# femtoUSB_r1_0_1.net
KiCad netlist of a schematic drawn in EAGLE
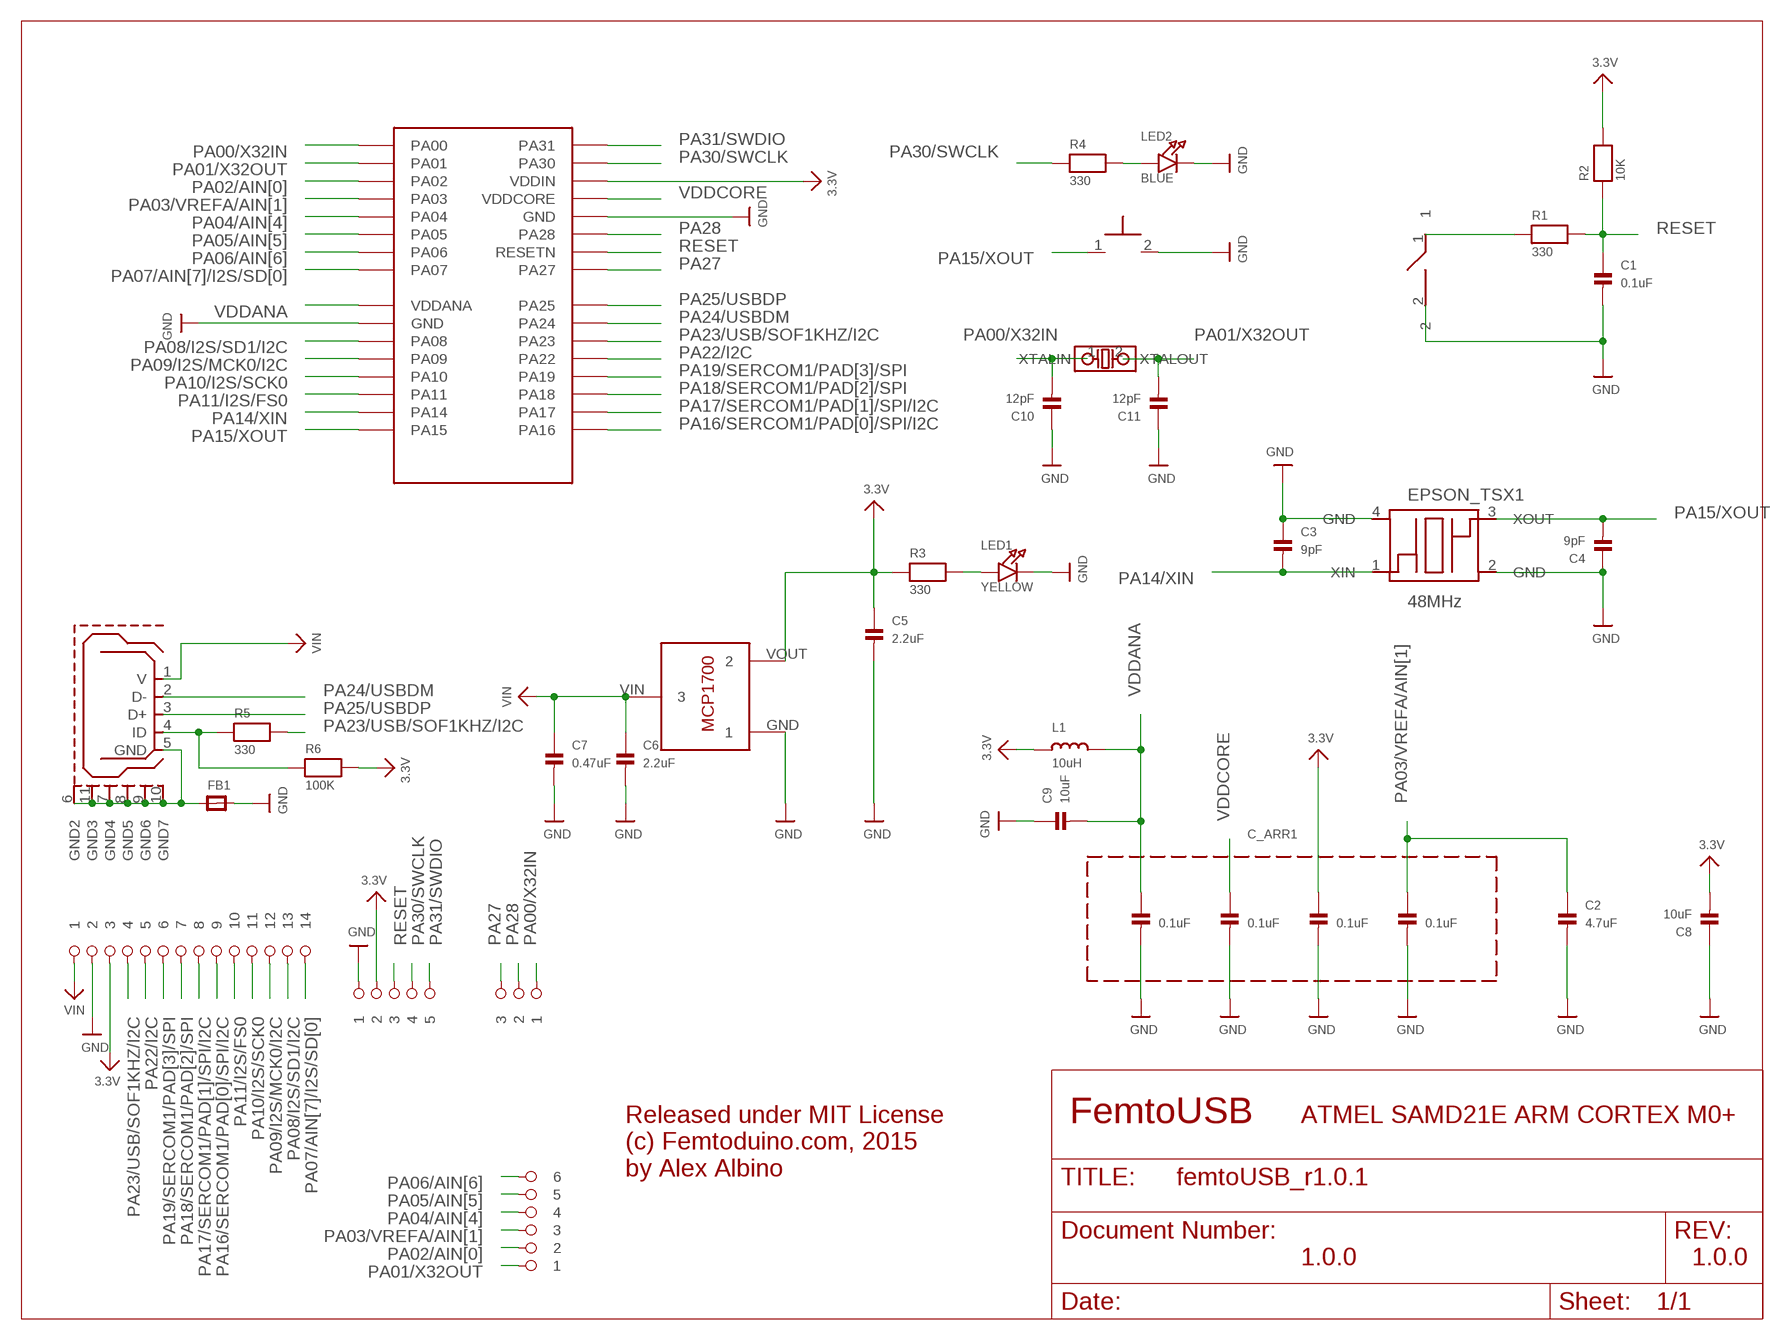
[diagram p0: schematic, sheet 1]

(export (version "E")
  (design (tool "Eeschema 10.0.6"))
  (components
    (comp (ref "BTN")
      (value "OMRON B3U-300P(M)")
      (footprint "eagle-import:SPST_SMD")
      (libsource (lib "eagle-import") (part "SPST_SMD"))
    )
    (comp (ref "C1")
      (value "0.1uF")
      (footprint "eagle-import:_0402MP")
      (libsource (lib "eagle-import") (part "CAP_CERAMIC_0402MP"))
    )
    (comp (ref "C2")
      (value "4.7uF")
      (footprint "eagle-import:_0402MP")
      (libsource (lib "eagle-import") (part "CAP_CERAMIC_0402MP"))
    )
    (comp (ref "C3")
      (value "9pF")
      (footprint "eagle-import:_0402MP")
      (libsource (lib "eagle-import") (part "CAP_CERAMIC_0402MP"))
    )
    (comp (ref "C4")
      (value "9pF")
      (footprint "eagle-import:_0402MP")
      (libsource (lib "eagle-import") (part "CAP_CERAMIC_0402MP"))
    )
    (comp (ref "C5")
      (value "2.2uF")
      (footprint "eagle-import:_0402MP")
      (libsource (lib "eagle-import") (part "CAP_CERAMIC_0402MP"))
    )
    (comp (ref "C6")
      (value "2.2uF")
      (footprint "eagle-import:_0402MP")
      (libsource (lib "eagle-import") (part "CAP_CERAMIC_0402MP"))
    )
    (comp (ref "C7")
      (value "0.47uF")
      (footprint "eagle-import:_0402MP")
      (libsource (lib "eagle-import") (part "CAP_CERAMIC_0402MP"))
    )
    (comp (ref "C8")
      (value "10uF")
      (footprint "eagle-import:_0402MP")
      (libsource (lib "eagle-import") (part "CAP_CERAMIC_0402MP"))
    )
    (comp (ref "C9")
      (value "10uF")
      (footprint "eagle-import:_0402MP")
      (libsource (lib "eagle-import") (part "CAP_CERAMIC_0402MP"))
    )
    (comp (ref "C10")
      (value "12pF")
      (footprint "eagle-import:_0402MP")
      (libsource (lib "eagle-import") (part "CAP_CERAMIC_0402MP"))
    )
    (comp (ref "C11")
      (value "12pF")
      (footprint "eagle-import:_0402MP")
      (libsource (lib "eagle-import") (part "CAP_CERAMIC_0402MP"))
    )
    (comp (ref "C_ARR1")
      (value "0.1uF")
      (footprint "eagle-import:CAPACITOR_ARRAY_1206_MONO_1X4")
      (libsource (lib "eagle-import") (part "KEMET_CERAMIC_CAPACITOR_ARRAY_1X4"))
    )
    (comp (ref "EPSON_TSX1")
      (value "48MHz")
      (footprint "eagle-import:TSX-3225")
      (fields (field (name "DIGIKEY_PART") "TSX-3225 32.0000MF15X-B-ND"))
      (libsource (lib "eagle-import") (part "TSX-3225"))
    )
    (comp (ref "FB1")
      (value "FERRITE_0603MP")
      (footprint "eagle-import:_0603MP")
      (libsource (lib "eagle-import") (part "FERRITE_0603MP"))
    )
    (comp (ref "IC1")
      (value "ATSAMD21E18A-MUT")
      (footprint "eagle-import:QFN32")
      (libsource (lib "eagle-import") (part "ATSAMD21E18A-MUT"))
    )
    (comp (ref "L1")
      (value "10uH")
      (footprint "eagle-import:_0603MP")
      (libsource (lib "eagle-import") (part "INDUCTOR_0603MP"))
    )
    (comp (ref "LDO_VREG")
      (value "MCP1700T-3302E/TT")
      (footprint "eagle-import:MCP1700T-3302E_TT")
      (libsource (lib "eagle-import") (part "MCP1700T-3302E/TT"))
    )
    (comp (ref "LED1")
      (value "YELLOW")
      (footprint "eagle-import:CHIPLED_0603_NOOUTLINE")
      (libsource (lib "eagle-import") (part "LED0603_NOOUTLINE"))
    )
    (comp (ref "LED2")
      (value "BLUE")
      (footprint "eagle-import:CHIPLED_0603_NOOUTLINE")
      (libsource (lib "eagle-import") (part "LED0603_NOOUTLINE"))
    )
    (comp (ref "MICRO_B_USB")
      (value "USB_MICROB")
      (footprint "eagle-import:USB_MICROB_PACKAGE")
      (libsource (lib "eagle-import") (part "USB_MICROB"))
    )
    (comp (ref "R1")
      (value "330")
      (footprint "eagle-import:_0402MP")
      (libsource (lib "eagle-import") (part "RESISTOR_0402MP"))
    )
    (comp (ref "R2")
      (value "10K")
      (footprint "eagle-import:_0402MP")
      (libsource (lib "eagle-import") (part "RESISTOR_0402MP"))
    )
    (comp (ref "R3")
      (value "330")
      (footprint "eagle-import:_0402MP")
      (libsource (lib "eagle-import") (part "RESISTOR_0402MP"))
    )
    (comp (ref "R4")
      (value "330")
      (footprint "eagle-import:_0402MP")
      (libsource (lib "eagle-import") (part "RESISTOR_0402MP"))
    )
    (comp (ref "R5")
      (value "330")
      (footprint "eagle-import:_0402MP")
      (libsource (lib "eagle-import") (part "RESISTOR_0402MP"))
    )
    (comp (ref "R6")
      (value "100K")
      (footprint "eagle-import:_0402MP")
      (libsource (lib "eagle-import") (part "RESISTOR_0402MP"))
    )
    (comp (ref "U$6")
      (value "1X14_ROUND")
      (footprint "eagle-import:1X14_ROUND")
      (libsource (lib "eagle-import") (part "1X14_ROUND"))
    )
    (comp (ref "U$7")
      (value "1X3_ROUND")
      (footprint "eagle-import:1X3_ROUND")
      (libsource (lib "eagle-import") (part "1X3_ROUND"))
    )
    (comp (ref "U$9")
      (value "1X5_ROUND")
      (footprint "eagle-import:1X5_ROUND")
      (libsource (lib "eagle-import") (part "1X5_ROUND"))
    )
    (comp (ref "U$12")
      (value "1X6_ROUND")
      (footprint "eagle-import:1X6_ROUND")
      (libsource (lib "eagle-import") (part "1X6_ROUND"))
    )
    (comp (ref "U$40")
      (value "ABS06-107-32.768KHZ-T")
      (footprint "eagle-import:ABS06-107-32.768KHZ-T")
      (libsource (lib "eagle-import") (part "ABS06-107-32.768KHZ-T"))
    )
    (comp (ref "U$43")
      (value "TACTILE_SWITCH_NO_GND_NO_BOSS")
      (footprint "eagle-import:SIDE_ACT_NO_GND_NO_BOSS")
      (libsource (lib "eagle-import") (part "TACTILE_SWITCH_NO_GND_NO_BOSS"))
    )
  )
  (nets
    (net (code "1") (name "/PA00{slash}X32IN") (class "Default")
      (node (ref "C10") (pin "2") (pinfunction "P$2_2") (pintype "passive"))
      (node (ref "IC1") (pin "1") (pinfunction "PA00_1") (pintype "bidirectional"))
      (node (ref "U$40") (pin "1") (pinfunction "XTALIN_1") (pintype "bidirectional"))
      (node (ref "U$7") (pin "P$1") (pinfunction "1_P$1") (pintype "bidirectional"))
    )
    (net (code "2") (name "/PA01{slash}X32OUT") (class "Default")
      (node (ref "C11") (pin "2") (pinfunction "P$2_2") (pintype "passive"))
      (node (ref "IC1") (pin "2") (pinfunction "PA01_2") (pintype "bidirectional"))
      (node (ref "U$12") (pin "P$1") (pinfunction "1_P$1") (pintype "bidirectional"))
      (node (ref "U$40") (pin "2") (pinfunction "XTALOUT_2") (pintype "bidirectional"))
    )
    (net (code "3") (name "/PA02{slash}AIN[0]") (class "Default")
      (node (ref "IC1") (pin "3") (pinfunction "PA02_3") (pintype "bidirectional"))
      (node (ref "U$12") (pin "P$2") (pinfunction "2_P$2") (pintype "bidirectional"))
    )
    (net (code "4") (name "/PA03{slash}VREFA{slash}AIN[1]") (class "Default")
      (node (ref "C2") (pin "1") (pinfunction "P$1_1") (pintype "passive"))
      (node (ref "C_ARR1") (pin "7") (pinfunction "P$7_7") (pintype "passive"))
      (node (ref "IC1") (pin "4") (pinfunction "PA03_4") (pintype "bidirectional"))
      (node (ref "U$12") (pin "P$3") (pinfunction "3_P$3") (pintype "bidirectional"))
    )
    (net (code "5") (name "/PA04{slash}AIN[4]") (class "Default")
      (node (ref "IC1") (pin "5") (pinfunction "PA04_5") (pintype "bidirectional"))
      (node (ref "U$12") (pin "P$4") (pinfunction "4_P$4") (pintype "bidirectional"))
    )
    (net (code "6") (name "/PA05{slash}AIN[5]") (class "Default")
      (node (ref "IC1") (pin "6") (pinfunction "PA05_6") (pintype "bidirectional"))
      (node (ref "U$12") (pin "P$5") (pinfunction "5_P$5") (pintype "bidirectional"))
    )
    (net (code "7") (name "/PA06{slash}AIN[6]") (class "Default")
      (node (ref "IC1") (pin "7") (pinfunction "PA06_7") (pintype "bidirectional"))
      (node (ref "U$12") (pin "P$6") (pinfunction "6_P$6") (pintype "bidirectional"))
    )
    (net (code "8") (name "/PA07{slash}AIN[7]{slash}I2S{slash}SD[0]") (class "Default")
      (node (ref "IC1") (pin "8") (pinfunction "PA07_8") (pintype "bidirectional"))
      (node (ref "U$6") (pin "P$14") (pinfunction "14_P$14") (pintype "bidirectional"))
    )
    (net (code "9") (name "/PA08{slash}I2S{slash}SD1{slash}I2C") (class "Default")
      (node (ref "IC1") (pin "11") (pinfunction "PA08_11") (pintype "bidirectional"))
      (node (ref "U$6") (pin "P$13") (pinfunction "13_P$13") (pintype "bidirectional"))
    )
    (net (code "10") (name "/PA09{slash}I2S{slash}MCK0{slash}I2C") (class "Default")
      (node (ref "IC1") (pin "12") (pinfunction "PA09_12") (pintype "bidirectional"))
      (node (ref "U$6") (pin "P$12") (pinfunction "12_P$12") (pintype "bidirectional"))
    )
    (net (code "11") (name "/PA10{slash}I2S{slash}SCK0") (class "Default")
      (node (ref "IC1") (pin "13") (pinfunction "PA10_13") (pintype "bidirectional"))
      (node (ref "U$6") (pin "P$11") (pinfunction "11_P$11") (pintype "bidirectional"))
    )
    (net (code "12") (name "/PA11{slash}I2S{slash}FS0") (class "Default")
      (node (ref "IC1") (pin "14") (pinfunction "PA11_14") (pintype "bidirectional"))
      (node (ref "U$6") (pin "P$10") (pinfunction "10_P$10") (pintype "bidirectional"))
    )
    (net (code "13") (name "/PA14{slash}XIN") (class "Default")
      (node (ref "C3") (pin "2") (pinfunction "P$2_2") (pintype "passive"))
      (node (ref "EPSON_TSX1") (pin "1") (pinfunction "XIN_1") (pintype "bidirectional"))
      (node (ref "IC1") (pin "15") (pinfunction "PA14_15") (pintype "bidirectional"))
    )
    (net (code "14") (name "/PA15{slash}XOUT") (class "Default")
      (node (ref "C4") (pin "2") (pinfunction "P$2_2") (pintype "passive"))
      (node (ref "EPSON_TSX1") (pin "3") (pinfunction "XOUT_3") (pintype "bidirectional"))
      (node (ref "IC1") (pin "16") (pinfunction "PA15_16") (pintype "bidirectional"))
      (node (ref "U$43") (pin "1") (pinfunction "1_1") (pintype "bidirectional"))
    )
    (net (code "15") (name "/PA16{slash}SERCOM1{slash}PAD[0]{slash}SPI{slash}I2C") (class "Default")
      (node (ref "IC1") (pin "17") (pinfunction "PA16_17") (pintype "bidirectional"))
      (node (ref "U$6") (pin "P$9") (pinfunction "9_P$9") (pintype "bidirectional"))
    )
    (net (code "16") (name "/PA17{slash}SERCOM1{slash}PAD[1]{slash}SPI{slash}I2C") (class "Default")
      (node (ref "IC1") (pin "18") (pinfunction "PA17_18") (pintype "bidirectional"))
      (node (ref "U$6") (pin "P$8") (pinfunction "8_P$8") (pintype "bidirectional"))
    )
    (net (code "17") (name "/PA18{slash}SERCOM1{slash}PAD[2]{slash}SPI") (class "Default")
      (node (ref "IC1") (pin "19") (pinfunction "PA18_19") (pintype "bidirectional"))
      (node (ref "U$6") (pin "P$7") (pinfunction "7_P$7") (pintype "bidirectional"))
    )
    (net (code "18") (name "/PA19{slash}SERCOM1{slash}PAD[3]{slash}SPI") (class "Default")
      (node (ref "IC1") (pin "20") (pinfunction "PA19_20") (pintype "bidirectional"))
      (node (ref "U$6") (pin "P$6") (pinfunction "6_P$6") (pintype "bidirectional"))
    )
    (net (code "19") (name "/PA22{slash}I2C") (class "Default")
      (node (ref "IC1") (pin "21") (pinfunction "PA22_21") (pintype "bidirectional"))
      (node (ref "U$6") (pin "P$5") (pinfunction "5_P$5") (pintype "bidirectional"))
    )
    (net (code "20") (name "/PA23{slash}USB{slash}SOF1KHZ{slash}I2C") (class "Default")
      (node (ref "IC1") (pin "22") (pinfunction "PA23_22") (pintype "bidirectional"))
      (node (ref "R5") (pin "2") (pinfunction "2_2") (pintype "passive"))
      (node (ref "U$6") (pin "P$4") (pinfunction "4_P$4") (pintype "bidirectional"))
    )
    (net (code "21") (name "/PA24{slash}USBDM") (class "Default")
      (node (ref "IC1") (pin "23") (pinfunction "PA24_23") (pintype "bidirectional"))
      (node (ref "MICRO_B_USB") (pin "2") (pinfunction "D-_2") (pintype "bidirectional"))
    )
    (net (code "22") (name "/PA25{slash}USBDP") (class "Default")
      (node (ref "IC1") (pin "24") (pinfunction "PA25_24") (pintype "bidirectional"))
      (node (ref "MICRO_B_USB") (pin "3") (pinfunction "D+_3") (pintype "bidirectional"))
    )
    (net (code "23") (name "/PA27") (class "Default")
      (node (ref "IC1") (pin "25") (pinfunction "PA27_25") (pintype "bidirectional"))
      (node (ref "U$7") (pin "P$3") (pinfunction "3_P$3") (pintype "bidirectional"))
    )
    (net (code "24") (name "/PA28") (class "Default")
      (node (ref "IC1") (pin "27") (pinfunction "PA28_27") (pintype "bidirectional"))
      (node (ref "U$7") (pin "P$2") (pinfunction "2_P$2") (pintype "bidirectional"))
    )
    (net (code "25") (name "/PA30{slash}SWCLK") (class "Default")
      (node (ref "IC1") (pin "31") (pinfunction "PA30_31") (pintype "bidirectional"))
      (node (ref "R4") (pin "1") (pinfunction "1_1") (pintype "passive"))
      (node (ref "U$9") (pin "P$4") (pinfunction "4_P$4") (pintype "bidirectional"))
    )
    (net (code "26") (name "/PA31{slash}SWDIO") (class "Default")
      (node (ref "IC1") (pin "32") (pinfunction "PA31_32") (pintype "bidirectional"))
      (node (ref "U$9") (pin "P$5") (pinfunction "5_P$5") (pintype "bidirectional"))
    )
    (net (code "27") (name "/RESET") (class "Default")
      (node (ref "C1") (pin "1") (pinfunction "P$1_1") (pintype "passive"))
      (node (ref "IC1") (pin "26") (pinfunction "RESETN_26") (pintype "bidirectional"))
      (node (ref "R1") (pin "2") (pinfunction "2_2") (pintype "passive"))
      (node (ref "R2") (pin "1") (pinfunction "1_1") (pintype "passive"))
      (node (ref "U$9") (pin "P$3") (pinfunction "3_P$3") (pintype "bidirectional"))
    )
    (net (code "28") (name "/VDDANA") (class "Default")
      (node (ref "C9") (pin "2") (pinfunction "P$2_2") (pintype "passive"))
      (node (ref "C_ARR1") (pin "1") (pinfunction "P$1_1") (pintype "passive"))
      (node (ref "IC1") (pin "9") (pinfunction "VDDANA_9") (pintype "bidirectional"))
      (node (ref "L1") (pin "2") (pinfunction "2_2") (pintype "passive"))
    )
    (net (code "29") (name "/VDDCORE") (class "Default")
      (node (ref "C_ARR1") (pin "3") (pinfunction "P$3_3") (pintype "passive"))
      (node (ref "IC1") (pin "29") (pinfunction "VDDCORE_29") (pintype "bidirectional"))
    )
    (net (code "30") (name "3.3V") (class "Default")
      (node (ref "C5") (pin "1") (pinfunction "P$1_1") (pintype "passive"))
      (node (ref "C8") (pin "2") (pinfunction "P$2_2") (pintype "passive"))
      (node (ref "C_ARR1") (pin "5") (pinfunction "P$5_5") (pintype "passive"))
      (node (ref "IC1") (pin "30") (pinfunction "VDDIN_30") (pintype "bidirectional"))
      (node (ref "L1") (pin "1") (pinfunction "1_1") (pintype "passive"))
      (node (ref "LDO_VREG") (pin "VOUT") (pinfunction "2_VOUT") (pintype "bidirectional"))
      (node (ref "R2") (pin "2") (pinfunction "2_2") (pintype "passive"))
      (node (ref "R3") (pin "1") (pinfunction "1_1") (pintype "passive"))
      (node (ref "R6") (pin "2") (pinfunction "2_2") (pintype "passive"))
      (node (ref "U$6") (pin "P$3") (pinfunction "3_P$3") (pintype "bidirectional"))
      (node (ref "U$9") (pin "P$2") (pinfunction "2_P$2") (pintype "bidirectional"))
    )
    (net (code "31") (name "GND") (class "Default")
      (node (ref "BTN") (pin "2") (pinfunction "2_2") (pintype "bidirectional"))
      (node (ref "C1") (pin "2") (pinfunction "P$2_2") (pintype "passive"))
      (node (ref "C10") (pin "1") (pinfunction "P$1_1") (pintype "passive"))
      (node (ref "C11") (pin "1") (pinfunction "P$1_1") (pintype "passive"))
      (node (ref "C2") (pin "2") (pinfunction "P$2_2") (pintype "passive"))
      (node (ref "C3") (pin "1") (pinfunction "P$1_1") (pintype "passive"))
      (node (ref "C4") (pin "1") (pinfunction "P$1_1") (pintype "passive"))
      (node (ref "C5") (pin "2") (pinfunction "P$2_2") (pintype "passive"))
      (node (ref "C6") (pin "2") (pinfunction "P$2_2") (pintype "passive"))
      (node (ref "C7") (pin "2") (pinfunction "P$2_2") (pintype "passive"))
      (node (ref "C8") (pin "1") (pinfunction "P$1_1") (pintype "passive"))
      (node (ref "C9") (pin "1") (pinfunction "P$1_1") (pintype "passive"))
      (node (ref "C_ARR1") (pin "2") (pinfunction "P$2_2") (pintype "passive"))
      (node (ref "C_ARR1") (pin "4") (pinfunction "P$4_4") (pintype "passive"))
      (node (ref "C_ARR1") (pin "6") (pinfunction "P$6_6") (pintype "passive"))
      (node (ref "C_ARR1") (pin "8") (pinfunction "P$8_8") (pintype "passive"))
      (node (ref "EPSON_TSX1") (pin "2") (pinfunction "GND_2") (pintype "bidirectional"))
      (node (ref "EPSON_TSX1") (pin "4") (pinfunction "GND_4") (pintype "bidirectional"))
      (node (ref "FB1") (pin "2") (pinfunction "P$2_2") (pintype "passive"))
      (node (ref "IC1") (pin "10") (pinfunction "GND_10") (pintype "bidirectional"))
      (node (ref "IC1") (pin "28") (pinfunction "GND_28") (pintype "bidirectional"))
      (node (ref "LDO_VREG") (pin "GND") (pinfunction "1_GND") (pintype "bidirectional"))
      (node (ref "LED1") (pin "C") (pinfunction "C_C") (pintype "passive"))
      (node (ref "LED2") (pin "C") (pinfunction "C_C") (pintype "passive"))
      (node (ref "U$43") (pin "2") (pinfunction "2_2") (pintype "bidirectional"))
      (node (ref "U$6") (pin "P$2") (pinfunction "2_P$2") (pintype "bidirectional"))
      (node (ref "U$9") (pin "P$1") (pinfunction "1_P$1") (pintype "bidirectional"))
    )
    (net (code "32") (name "Net-(BTN-Pad1)") (class "Default")
      (node (ref "BTN") (pin "1") (pinfunction "1_1") (pintype "bidirectional"))
      (node (ref "R1") (pin "1") (pinfunction "1_1") (pintype "passive"))
    )
    (net (code "33") (name "Net-(FB1-P$1)") (class "Default")
      (node (ref "FB1") (pin "1") (pinfunction "P$1_1") (pintype "passive"))
      (node (ref "MICRO_B_USB") (pin "10") (pinfunction "GND7_10") (pintype "bidirectional"))
      (node (ref "MICRO_B_USB") (pin "11") (pinfunction "GND3_11") (pintype "bidirectional"))
      (node (ref "MICRO_B_USB") (pin "5") (pinfunction "GND_5") (pintype "bidirectional"))
      (node (ref "MICRO_B_USB") (pin "6") (pinfunction "GND2_6") (pintype "bidirectional"))
      (node (ref "MICRO_B_USB") (pin "7") (pinfunction "GND4_7") (pintype "bidirectional"))
      (node (ref "MICRO_B_USB") (pin "8") (pinfunction "GND5_8") (pintype "bidirectional"))
      (node (ref "MICRO_B_USB") (pin "9") (pinfunction "GND6_9") (pintype "bidirectional"))
    )
    (net (code "34") (name "Net-(LED1-PadA)") (class "Default")
      (node (ref "LED1") (pin "A") (pinfunction "A_A") (pintype "passive"))
      (node (ref "R3") (pin "2") (pinfunction "2_2") (pintype "passive"))
    )
    (net (code "35") (name "Net-(LED2-PadA)") (class "Default")
      (node (ref "LED2") (pin "A") (pinfunction "A_A") (pintype "passive"))
      (node (ref "R4") (pin "2") (pinfunction "2_2") (pintype "passive"))
    )
    (net (code "36") (name "Net-(MICRO_B_USB-ID)") (class "Default")
      (node (ref "MICRO_B_USB") (pin "4") (pinfunction "ID_4") (pintype "bidirectional"))
      (node (ref "R5") (pin "1") (pinfunction "1_1") (pintype "passive"))
      (node (ref "R6") (pin "1") (pinfunction "1_1") (pintype "passive"))
    )
    (net (code "37") (name "VIN") (class "Default")
      (node (ref "C6") (pin "1") (pinfunction "P$1_1") (pintype "passive"))
      (node (ref "C7") (pin "1") (pinfunction "P$1_1") (pintype "passive"))
      (node (ref "LDO_VREG") (pin "VIN") (pinfunction "3_VIN") (pintype "bidirectional"))
      (node (ref "MICRO_B_USB") (pin "1") (pinfunction "V_1") (pintype "bidirectional"))
      (node (ref "U$6") (pin "P$1") (pinfunction "1_P$1") (pintype "bidirectional"))
    )
  )
)
